# IDEAdapterDouble.net
KiCad netlist of a schematic drawn in EAGLE
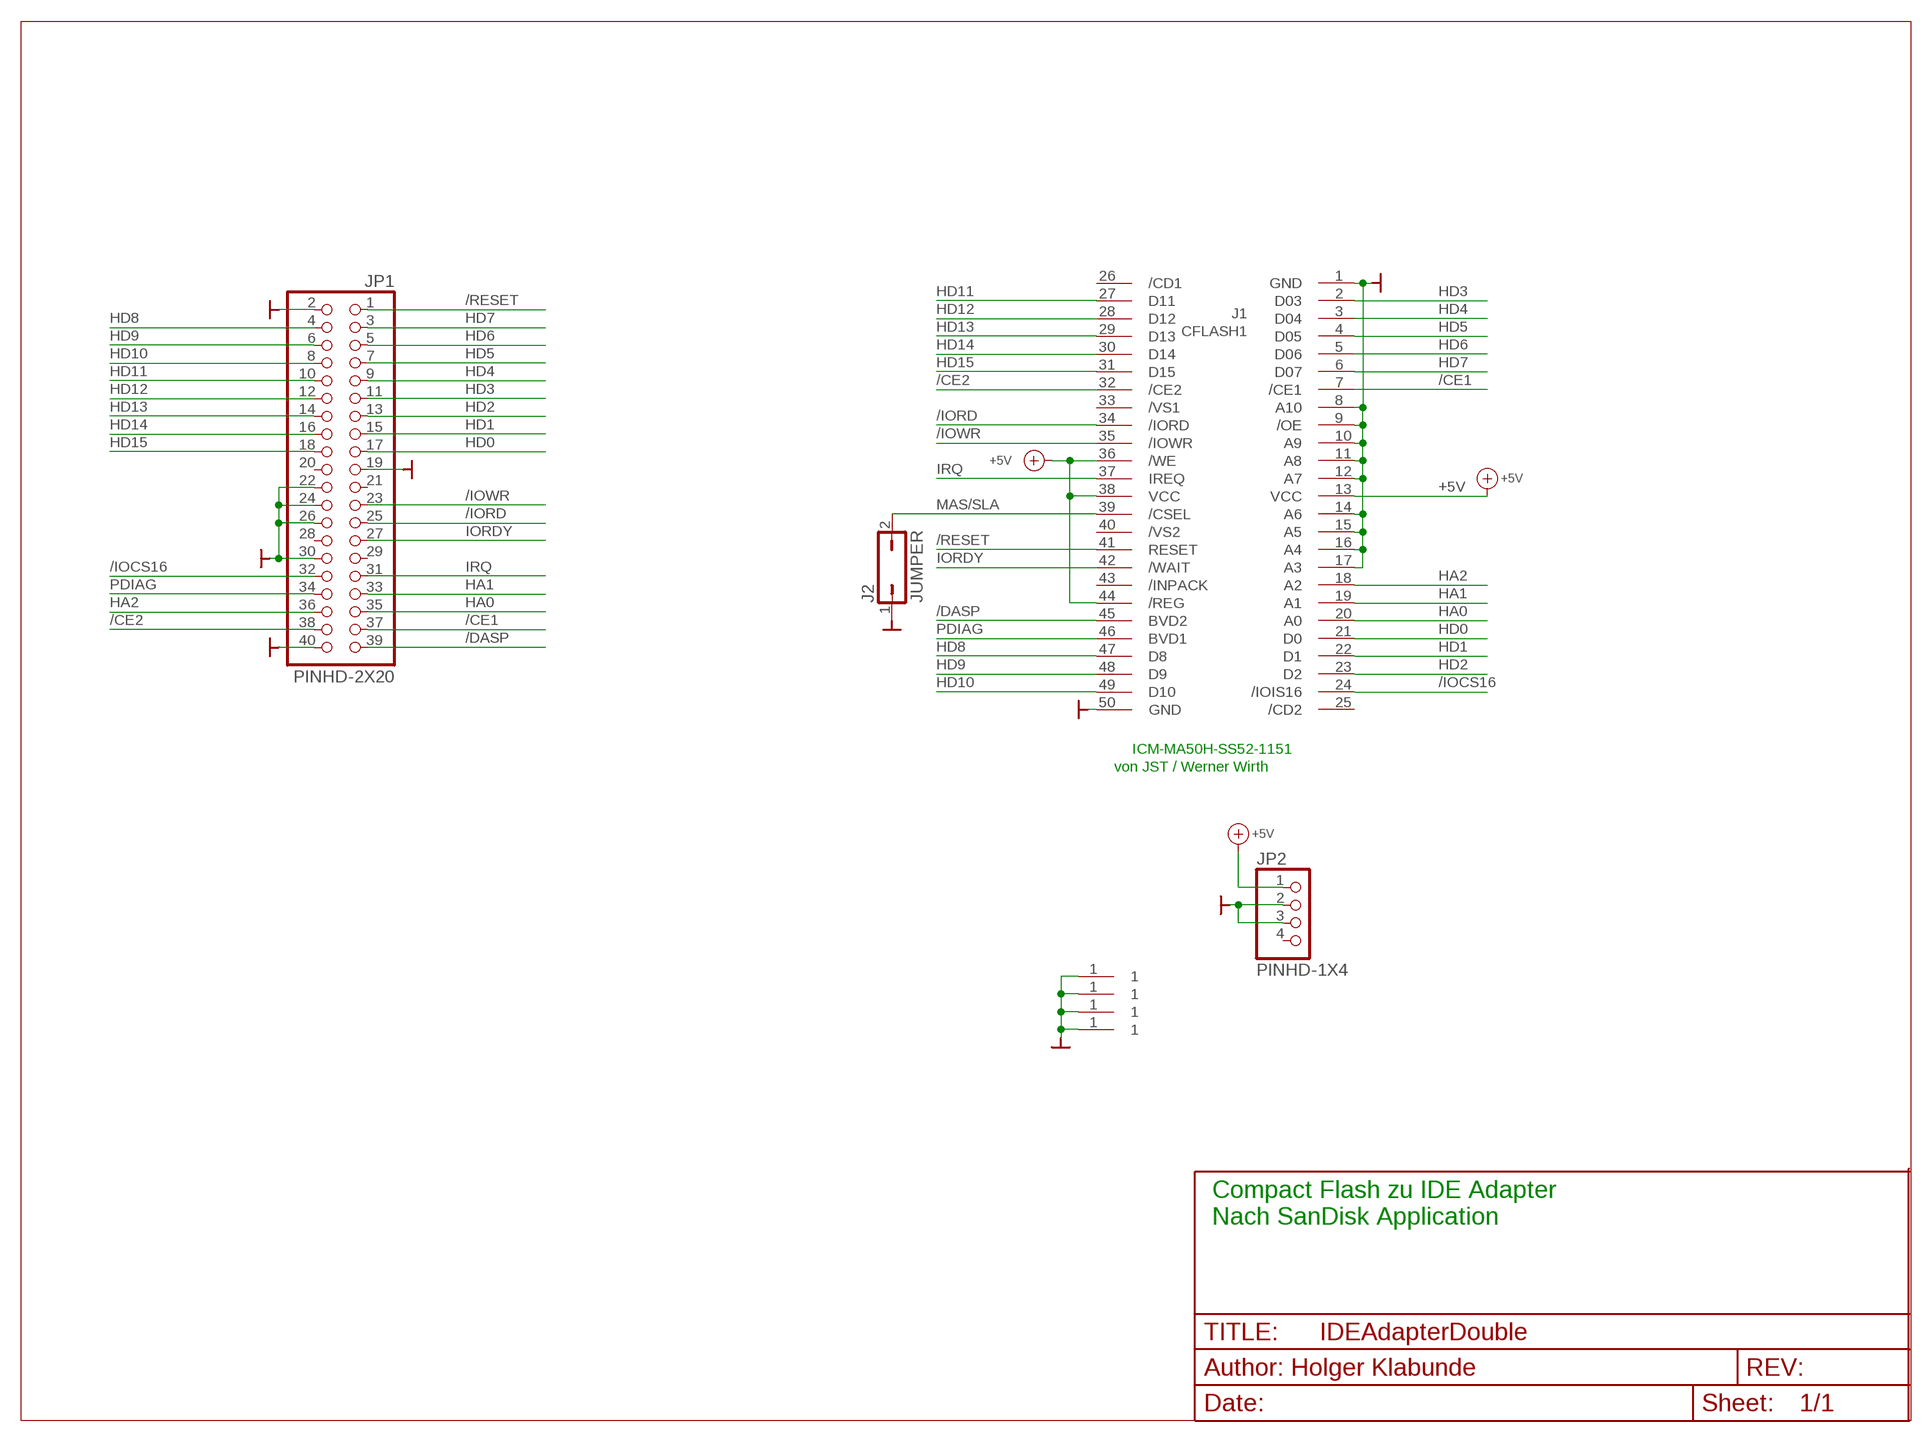
[diagram p0: schematic, sheet 1]

(export (version "E")
  (design (tool "Eeschema 10.0.6"))
  (components
    (comp (ref "J1")
      (value "CFLASH1")
      (footprint "eagle-import:CFSMT")
      (libsource (lib "eagle-import") (part "CFLASH1"))
    )
    (comp (ref "J2")
      (value "JUMPER")
      (footprint "eagle-import:JP1")
      (libsource (lib "eagle-import") (part "JP1Q"))
    )
    (comp (ref "JP1")
      (value "PINHD-2X20")
      (footprint "eagle-import:2X20")
      (libsource (lib "eagle-import") (part "PINHD-2X20"))
    )
    (comp (ref "JP2")
      (value "PINHD-1X4")
      (footprint "eagle-import:1X04")
      (libsource (lib "eagle-import") (part "PINHD-1X4"))
    )
    (comp (ref "U$13")
      (value "BOHRUNG")
      (footprint "eagle-import:BOHRUNG")
      (libsource (lib "eagle-import") (part "BOHRUNG"))
    )
    (comp (ref "U$14")
      (value "BOHRUNG")
      (footprint "eagle-import:BOHRUNG")
      (libsource (lib "eagle-import") (part "BOHRUNG"))
    )
    (comp (ref "U$16")
      (value "BOHRUNG")
      (footprint "eagle-import:BOHRUNG")
      (libsource (lib "eagle-import") (part "BOHRUNG"))
    )
    (comp (ref "U$17")
      (value "BOHRUNG")
      (footprint "eagle-import:BOHRUNG")
      (libsource (lib "eagle-import") (part "BOHRUNG"))
    )
  )
  (nets
    (net (code "1") (name "+5V") (class "Default")
      (node (ref "J1") (pin "13") (pinfunction "VCC_13") (pintype "power_in"))
      (node (ref "J1") (pin "36") (pinfunction "/WE_36") (pintype "input"))
      (node (ref "J1") (pin "38") (pinfunction "VCC_38") (pintype "power_in"))
      (node (ref "J1") (pin "44") (pinfunction "/REG_44") (pintype "input"))
      (node (ref "JP2") (pin "1") (pinfunction "1_1") (pintype "passive"))
    )
    (net (code "2") (name "/HA0") (class "Default")
      (node (ref "J1") (pin "20") (pinfunction "A0_20") (pintype "input"))
      (node (ref "JP1") (pin "35") (pinfunction "35_35") (pintype "passive"))
    )
    (net (code "3") (name "/HA1") (class "Default")
      (node (ref "J1") (pin "19") (pinfunction "A1_19") (pintype "input"))
      (node (ref "JP1") (pin "33") (pinfunction "33_33") (pintype "passive"))
    )
    (net (code "4") (name "/HA2") (class "Default")
      (node (ref "J1") (pin "18") (pinfunction "A2_18") (pintype "input"))
      (node (ref "JP1") (pin "36") (pinfunction "36_36") (pintype "passive"))
    )
    (net (code "5") (name "/HD0") (class "Default")
      (node (ref "J1") (pin "21") (pinfunction "D0_21") (pintype "bidirectional"))
      (node (ref "JP1") (pin "17") (pinfunction "17_17") (pintype "passive"))
    )
    (net (code "6") (name "/HD1") (class "Default")
      (node (ref "J1") (pin "22") (pinfunction "D1_22") (pintype "bidirectional"))
      (node (ref "JP1") (pin "15") (pinfunction "15_15") (pintype "passive"))
    )
    (net (code "7") (name "/HD2") (class "Default")
      (node (ref "J1") (pin "23") (pinfunction "D2_23") (pintype "bidirectional"))
      (node (ref "JP1") (pin "13") (pinfunction "13_13") (pintype "passive"))
    )
    (net (code "8") (name "/HD3") (class "Default")
      (node (ref "J1") (pin "2") (pinfunction "D03_2") (pintype "bidirectional"))
      (node (ref "JP1") (pin "11") (pinfunction "11_11") (pintype "passive"))
    )
    (net (code "9") (name "/HD4") (class "Default")
      (node (ref "J1") (pin "3") (pinfunction "D04_3") (pintype "bidirectional"))
      (node (ref "JP1") (pin "9") (pinfunction "9_9") (pintype "passive"))
    )
    (net (code "10") (name "/HD5") (class "Default")
      (node (ref "J1") (pin "4") (pinfunction "D05_4") (pintype "bidirectional"))
      (node (ref "JP1") (pin "7") (pinfunction "7_7") (pintype "passive"))
    )
    (net (code "11") (name "/HD6") (class "Default")
      (node (ref "J1") (pin "5") (pinfunction "D06_5") (pintype "bidirectional"))
      (node (ref "JP1") (pin "5") (pinfunction "5_5") (pintype "passive"))
    )
    (net (code "12") (name "/HD7") (class "Default")
      (node (ref "J1") (pin "6") (pinfunction "D07_6") (pintype "bidirectional"))
      (node (ref "JP1") (pin "3") (pinfunction "3_3") (pintype "passive"))
    )
    (net (code "13") (name "/HD8") (class "Default")
      (node (ref "J1") (pin "47") (pinfunction "D8_47") (pintype "bidirectional"))
      (node (ref "JP1") (pin "4") (pinfunction "4_4") (pintype "passive"))
    )
    (net (code "14") (name "/HD9") (class "Default")
      (node (ref "J1") (pin "48") (pinfunction "D9_48") (pintype "bidirectional"))
      (node (ref "JP1") (pin "6") (pinfunction "6_6") (pintype "passive"))
    )
    (net (code "15") (name "/HD10") (class "Default")
      (node (ref "J1") (pin "49") (pinfunction "D10_49") (pintype "bidirectional"))
      (node (ref "JP1") (pin "8") (pinfunction "8_8") (pintype "passive"))
    )
    (net (code "16") (name "/HD11") (class "Default")
      (node (ref "J1") (pin "27") (pinfunction "D11_27") (pintype "bidirectional"))
      (node (ref "JP1") (pin "10") (pinfunction "10_10") (pintype "passive"))
    )
    (net (code "17") (name "/HD12") (class "Default")
      (node (ref "J1") (pin "28") (pinfunction "D12_28") (pintype "bidirectional"))
      (node (ref "JP1") (pin "12") (pinfunction "12_12") (pintype "passive"))
    )
    (net (code "18") (name "/HD13") (class "Default")
      (node (ref "J1") (pin "29") (pinfunction "D13_29") (pintype "bidirectional"))
      (node (ref "JP1") (pin "14") (pinfunction "14_14") (pintype "passive"))
    )
    (net (code "19") (name "/HD14") (class "Default")
      (node (ref "J1") (pin "30") (pinfunction "D14_30") (pintype "bidirectional"))
      (node (ref "JP1") (pin "16") (pinfunction "16_16") (pintype "passive"))
    )
    (net (code "20") (name "/HD15") (class "Default")
      (node (ref "J1") (pin "31") (pinfunction "D15_31") (pintype "bidirectional"))
      (node (ref "JP1") (pin "18") (pinfunction "18_18") (pintype "passive"))
    )
    (net (code "21") (name "/IORDY") (class "Default")
      (node (ref "J1") (pin "42") (pinfunction "/WAIT_42") (pintype "bidirectional"))
      (node (ref "JP1") (pin "27") (pinfunction "27_27") (pintype "passive"))
    )
    (net (code "22") (name "/IRQ") (class "Default")
      (node (ref "J1") (pin "37") (pinfunction "IREQ_37") (pintype "bidirectional"))
      (node (ref "JP1") (pin "31") (pinfunction "31_31") (pintype "passive"))
    )
    (net (code "23") (name "/MAS{slash}SLA") (class "Default")
      (node (ref "J1") (pin "39") (pinfunction "/CSEL_39") (pintype "input"))
      (node (ref "J2") (pin "2") (pinfunction "2_2") (pintype "passive"))
    )
    (net (code "24") (name "/PDIAG") (class "Default")
      (node (ref "J1") (pin "46") (pinfunction "BVD1_46") (pintype "input"))
      (node (ref "JP1") (pin "34") (pinfunction "34_34") (pintype "passive"))
    )
    (net (code "25") (name "/{slash}CE1") (class "Default")
      (node (ref "J1") (pin "7") (pinfunction "/CE1_7") (pintype "input"))
      (node (ref "JP1") (pin "37") (pinfunction "37_37") (pintype "passive"))
    )
    (net (code "26") (name "/{slash}CE2") (class "Default")
      (node (ref "J1") (pin "32") (pinfunction "/CE2_32") (pintype "input"))
      (node (ref "JP1") (pin "38") (pinfunction "38_38") (pintype "passive"))
    )
    (net (code "27") (name "/{slash}DASP") (class "Default")
      (node (ref "J1") (pin "45") (pinfunction "BVD2_45") (pintype "input"))
      (node (ref "JP1") (pin "39") (pinfunction "39_39") (pintype "passive"))
    )
    (net (code "28") (name "/{slash}IOCS16") (class "Default")
      (node (ref "J1") (pin "24") (pinfunction "/IOIS16_24") (pintype "input"))
      (node (ref "JP1") (pin "32") (pinfunction "32_32") (pintype "passive"))
    )
    (net (code "29") (name "/{slash}IORD") (class "Default")
      (node (ref "J1") (pin "34") (pinfunction "/IORD_34") (pintype "input"))
      (node (ref "JP1") (pin "25") (pinfunction "25_25") (pintype "passive"))
    )
    (net (code "30") (name "/{slash}IOWR") (class "Default")
      (node (ref "J1") (pin "35") (pinfunction "/IOWR_35") (pintype "input"))
      (node (ref "JP1") (pin "23") (pinfunction "23_23") (pintype "passive"))
    )
    (net (code "31") (name "/{slash}RESET") (class "Default")
      (node (ref "J1") (pin "41") (pinfunction "RESET_41") (pintype "input"))
      (node (ref "JP1") (pin "1") (pinfunction "1_1") (pintype "passive"))
    )
    (net (code "32") (name "GND") (class "Default")
      (node (ref "J1") (pin "1") (pinfunction "GND_1") (pintype "power_in"))
      (node (ref "J1") (pin "10") (pinfunction "A9_10") (pintype "input"))
      (node (ref "J1") (pin "11") (pinfunction "A8_11") (pintype "input"))
      (node (ref "J1") (pin "12") (pinfunction "A7_12") (pintype "input"))
      (node (ref "J1") (pin "14") (pinfunction "A6_14") (pintype "input"))
      (node (ref "J1") (pin "15") (pinfunction "A5_15") (pintype "input"))
      (node (ref "J1") (pin "16") (pinfunction "A4_16") (pintype "input"))
      (node (ref "J1") (pin "17") (pinfunction "A3_17") (pintype "input"))
      (node (ref "J1") (pin "50") (pinfunction "GND_50") (pintype "power_in"))
      (node (ref "J1") (pin "8") (pinfunction "A10_8") (pintype "input"))
      (node (ref "J1") (pin "9") (pinfunction "/OE_9") (pintype "input"))
      (node (ref "J2") (pin "1") (pinfunction "1_1") (pintype "passive"))
      (node (ref "JP1") (pin "19") (pinfunction "19_19") (pintype "passive"))
      (node (ref "JP1") (pin "2") (pinfunction "2_2") (pintype "passive"))
      (node (ref "JP1") (pin "22") (pinfunction "22_22") (pintype "passive"))
      (node (ref "JP1") (pin "24") (pinfunction "24_24") (pintype "passive"))
      (node (ref "JP1") (pin "26") (pinfunction "26_26") (pintype "passive"))
      (node (ref "JP1") (pin "30") (pinfunction "30_30") (pintype "passive"))
      (node (ref "JP1") (pin "40") (pinfunction "40_40") (pintype "passive"))
      (node (ref "JP2") (pin "2") (pinfunction "2_2") (pintype "passive"))
      (node (ref "JP2") (pin "3") (pinfunction "3_3") (pintype "passive"))
      (node (ref "U$13") (pin "1") (pinfunction "1_1") (pintype "bidirectional"))
      (node (ref "U$14") (pin "1") (pinfunction "1_1") (pintype "bidirectional"))
      (node (ref "U$16") (pin "1") (pinfunction "1_1") (pintype "bidirectional"))
      (node (ref "U$17") (pin "1") (pinfunction "1_1") (pintype "bidirectional"))
    )
    (net (code "33") (name "unconnected-(J1-{slash}CD1-Pad26)") (class "Default")
      (node (ref "J1") (pin "26") (pinfunction "/CD1_26") (pintype "input"))
    )
    (net (code "34") (name "unconnected-(J1-{slash}CD2-Pad25)") (class "Default")
      (node (ref "J1") (pin "25") (pinfunction "/CD2_25") (pintype "input"))
    )
    (net (code "35") (name "unconnected-(J1-{slash}INPACK-Pad43)") (class "Default")
      (node (ref "J1") (pin "43") (pinfunction "/INPACK_43") (pintype "input"))
    )
    (net (code "36") (name "unconnected-(J1-{slash}VS1-Pad33)") (class "Default")
      (node (ref "J1") (pin "33") (pinfunction "/VS1_33") (pintype "input"))
    )
    (net (code "37") (name "unconnected-(J1-{slash}VS2-Pad40)") (class "Default")
      (node (ref "J1") (pin "40") (pinfunction "/VS2_40") (pintype "input"))
    )
    (net (code "38") (name "unconnected-(JP1-Pad20)") (class "Default")
      (node (ref "JP1") (pin "20") (pinfunction "20_20") (pintype "passive"))
    )
    (net (code "39") (name "unconnected-(JP1-Pad21)") (class "Default")
      (node (ref "JP1") (pin "21") (pinfunction "21_21") (pintype "passive"))
    )
    (net (code "40") (name "unconnected-(JP1-Pad28)") (class "Default")
      (node (ref "JP1") (pin "28") (pinfunction "28_28") (pintype "passive"))
    )
    (net (code "41") (name "unconnected-(JP1-Pad29)") (class "Default")
      (node (ref "JP1") (pin "29") (pinfunction "29_29") (pintype "passive"))
    )
    (net (code "42") (name "unconnected-(JP2-Pad4)") (class "Default")
      (node (ref "JP2") (pin "4") (pinfunction "4_4") (pintype "passive"))
    )
  )
)
